# SimpleSeqArd_a10_added_missing_resistors.net
KiCad netlist of a schematic drawn in EAGLE
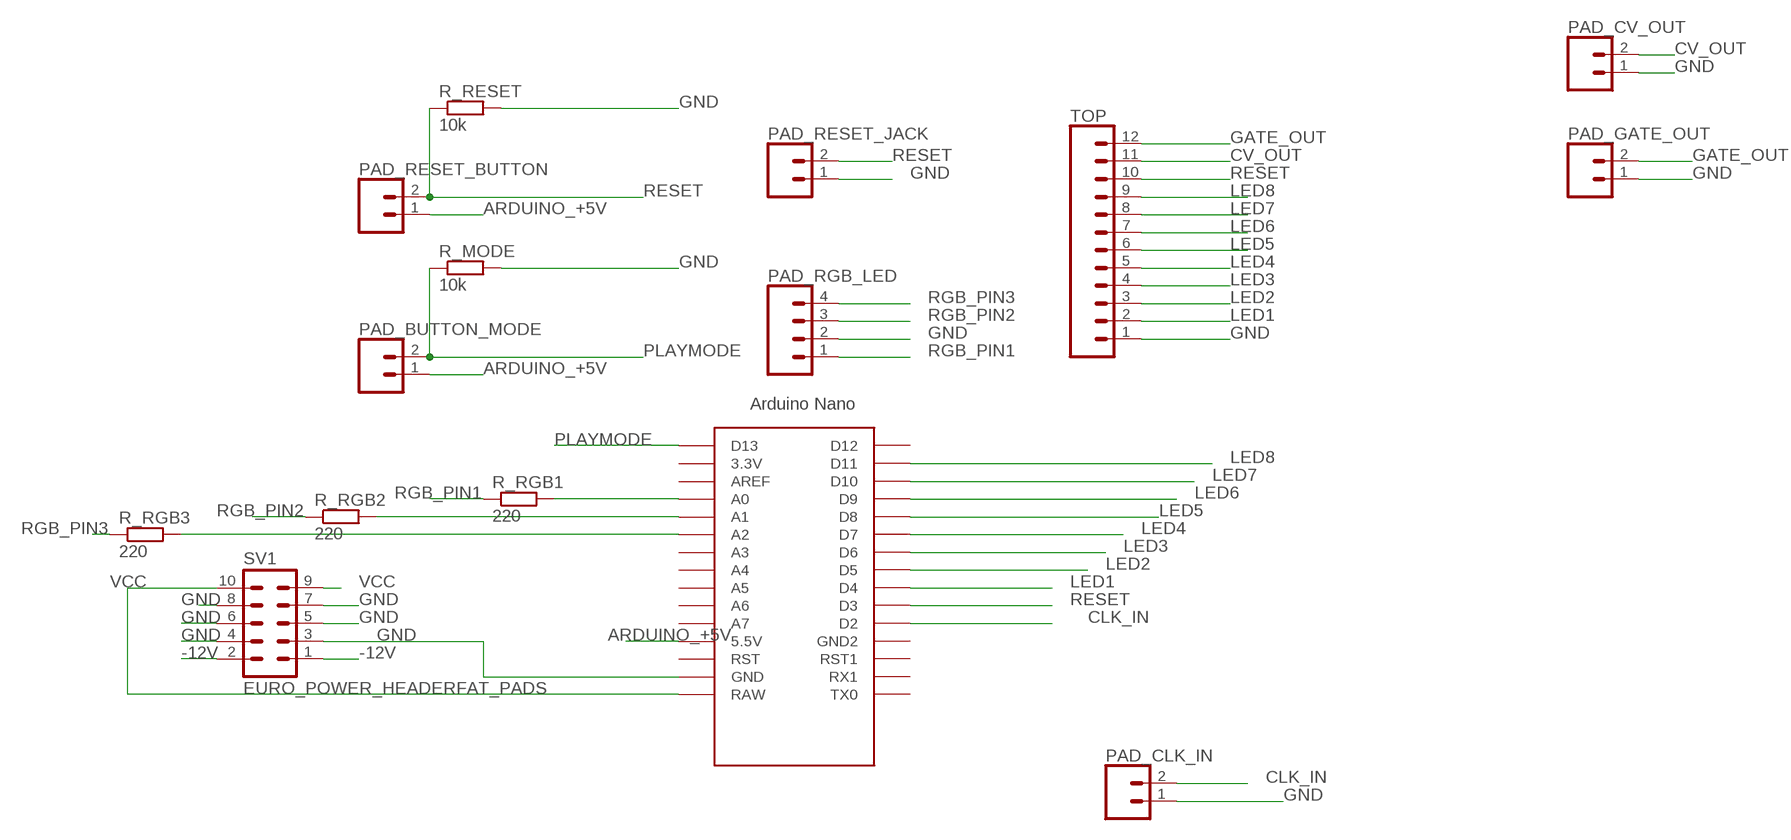
[diagram p0: schematic, sheet 1]

(export (version "E")
  (design (tool "Eeschema 10.0.6"))
  (components
    (comp (ref "PAD_BUTTON_MODE")
      (value "CONN_02PTH3")
      (footprint "eagle-import:1X02_LONGPADS")
      (libsource (lib "eagle-import") (part "CONN_02PTH3"))
    )
    (comp (ref "PAD_CLK_IN")
      (value "CONN_02PTH3")
      (footprint "eagle-import:1X02_LONGPADS")
      (libsource (lib "eagle-import") (part "CONN_02PTH3"))
    )
    (comp (ref "PAD_CV_OUT")
      (value "CONN_02PTH3")
      (footprint "eagle-import:1X02_LONGPADS")
      (libsource (lib "eagle-import") (part "CONN_02PTH3"))
    )
    (comp (ref "PAD_GATE_OUT")
      (value "CONN_02PTH3")
      (footprint "eagle-import:1X02_LONGPADS")
      (libsource (lib "eagle-import") (part "CONN_02PTH3"))
    )
    (comp (ref "PAD_RESET_BUTTON")
      (value "CONN_02PTH3")
      (footprint "eagle-import:1X02_LONGPADS")
      (libsource (lib "eagle-import") (part "CONN_02PTH3"))
    )
    (comp (ref "PAD_RESET_JACK")
      (value "CONN_02PTH3")
      (footprint "eagle-import:1X02_LONGPADS")
      (libsource (lib "eagle-import") (part "CONN_02PTH3"))
    )
    (comp (ref "PAD_RGB_LED")
      (value "CONN_04LONGPADS")
      (footprint "eagle-import:1X04_LONGPADS")
      (libsource (lib "eagle-import") (part "CONN_04LONGPADS"))
    )
    (comp (ref "R_MODE")
      (value "10k")
      (footprint "eagle-import:VERTICAL_RESISTOR")
      (libsource (lib "eagle-import") (part "RESISTORVERTICAL"))
    )
    (comp (ref "R_RESET")
      (value "10k")
      (footprint "eagle-import:VERTICAL_RESISTOR")
      (libsource (lib "eagle-import") (part "RESISTORVERTICAL"))
    )
    (comp (ref "R_RGB1")
      (value "220")
      (footprint "eagle-import:VERTICAL_RESISTOR")
      (libsource (lib "eagle-import") (part "RESISTORVERTICAL"))
    )
    (comp (ref "R_RGB2")
      (value "220")
      (footprint "eagle-import:VERTICAL_RESISTOR")
      (libsource (lib "eagle-import") (part "RESISTORVERTICAL"))
    )
    (comp (ref "R_RGB3")
      (value "220")
      (footprint "eagle-import:VERTICAL_RESISTOR")
      (libsource (lib "eagle-import") (part "RESISTORVERTICAL"))
    )
    (comp (ref "SV1")
      (value "EURO_POWER_HEADERFAT_PADS")
      (footprint "eagle-import:EURO_PWR_HEADER_FAT")
      (libsource (lib "eagle-import") (part "EURO_POWER_HEADERFAT_PADS"))
    )
    (comp (ref "TOP")
      (value "CONN_12LONGPADS")
      (footprint "eagle-import:1X12_LONGPADS")
      (libsource (lib "eagle-import") (part "CONN_12LONGPADS"))
    )
    (comp (ref "U$1")
      (value "NANO")
      (footprint "eagle-import:NANO")
      (libsource (lib "eagle-import") (part "NANO"))
    )
  )
  (nets
    (net (code "1") (name "/-12V") (class "Default")
      (node (ref "SV1") (pin "1") (pinfunction "1_1") (pintype "passive"))
      (node (ref "SV1") (pin "2") (pinfunction "2_2") (pintype "passive"))
    )
    (net (code "2") (name "/ARDUINO_+5V") (class "Default")
      (node (ref "PAD_BUTTON_MODE") (pin "1") (pinfunction "1_1") (pintype "passive"))
      (node (ref "PAD_RESET_BUTTON") (pin "1") (pinfunction "1_1") (pintype "passive"))
      (node (ref "U$1") (pin "5V") (pinfunction "5.5V_5V") (pintype "bidirectional"))
    )
    (net (code "3") (name "/CLK_IN") (class "Default")
      (node (ref "PAD_CLK_IN") (pin "2") (pinfunction "2_2") (pintype "passive"))
      (node (ref "U$1") (pin "D2") (pinfunction "D2_D2") (pintype "bidirectional"))
    )
    (net (code "4") (name "/CV_OUT") (class "Default")
      (node (ref "PAD_CV_OUT") (pin "2") (pinfunction "2_2") (pintype "passive"))
      (node (ref "TOP") (pin "11") (pinfunction "11_11") (pintype "passive"))
    )
    (net (code "5") (name "/GATE_OUT") (class "Default")
      (node (ref "PAD_GATE_OUT") (pin "2") (pinfunction "2_2") (pintype "passive"))
      (node (ref "TOP") (pin "12") (pinfunction "12_12") (pintype "passive"))
    )
    (net (code "6") (name "/GND") (class "Default")
      (node (ref "PAD_CLK_IN") (pin "1") (pinfunction "1_1") (pintype "passive"))
      (node (ref "PAD_CV_OUT") (pin "1") (pinfunction "1_1") (pintype "passive"))
      (node (ref "PAD_GATE_OUT") (pin "1") (pinfunction "1_1") (pintype "passive"))
      (node (ref "PAD_RESET_JACK") (pin "1") (pinfunction "1_1") (pintype "passive"))
      (node (ref "PAD_RGB_LED") (pin "2") (pinfunction "2_2") (pintype "passive"))
      (node (ref "R_MODE") (pin "2") (pinfunction "2_2") (pintype "passive"))
      (node (ref "R_RESET") (pin "2") (pinfunction "2_2") (pintype "passive"))
      (node (ref "SV1") (pin "3") (pinfunction "3_3") (pintype "passive"))
      (node (ref "SV1") (pin "4") (pinfunction "4_4") (pintype "passive"))
      (node (ref "SV1") (pin "5") (pinfunction "5_5") (pintype "passive"))
      (node (ref "SV1") (pin "6") (pinfunction "6_6") (pintype "passive"))
      (node (ref "SV1") (pin "7") (pinfunction "7_7") (pintype "passive"))
      (node (ref "SV1") (pin "8") (pinfunction "8_8") (pintype "passive"))
      (node (ref "TOP") (pin "1") (pinfunction "1_1") (pintype "passive"))
      (node (ref "U$1") (pin "GND") (pinfunction "GND_GND") (pintype "bidirectional"))
    )
    (net (code "7") (name "/LED1") (class "Default")
      (node (ref "TOP") (pin "2") (pinfunction "2_2") (pintype "passive"))
      (node (ref "U$1") (pin "D4") (pinfunction "D4_D4") (pintype "bidirectional"))
    )
    (net (code "8") (name "/LED2") (class "Default")
      (node (ref "TOP") (pin "3") (pinfunction "3_3") (pintype "passive"))
      (node (ref "U$1") (pin "D5") (pinfunction "D5_D5") (pintype "bidirectional"))
    )
    (net (code "9") (name "/LED3") (class "Default")
      (node (ref "TOP") (pin "4") (pinfunction "4_4") (pintype "passive"))
      (node (ref "U$1") (pin "D6") (pinfunction "D6_D6") (pintype "bidirectional"))
    )
    (net (code "10") (name "/LED4") (class "Default")
      (node (ref "TOP") (pin "5") (pinfunction "5_5") (pintype "passive"))
      (node (ref "U$1") (pin "D7") (pinfunction "D7_D7") (pintype "bidirectional"))
    )
    (net (code "11") (name "/LED5") (class "Default")
      (node (ref "TOP") (pin "6") (pinfunction "6_6") (pintype "passive"))
      (node (ref "U$1") (pin "D8") (pinfunction "D8_D8") (pintype "bidirectional"))
    )
    (net (code "12") (name "/LED6") (class "Default")
      (node (ref "TOP") (pin "7") (pinfunction "7_7") (pintype "passive"))
      (node (ref "U$1") (pin "D9") (pinfunction "D9_D9") (pintype "bidirectional"))
    )
    (net (code "13") (name "/LED7") (class "Default")
      (node (ref "TOP") (pin "8") (pinfunction "8_8") (pintype "passive"))
      (node (ref "U$1") (pin "D10") (pinfunction "D10_D10") (pintype "bidirectional"))
    )
    (net (code "14") (name "/LED8") (class "Default")
      (node (ref "TOP") (pin "9") (pinfunction "9_9") (pintype "passive"))
      (node (ref "U$1") (pin "D11") (pinfunction "D11_D11") (pintype "bidirectional"))
    )
    (net (code "15") (name "/PLAYMODE") (class "Default")
      (node (ref "PAD_BUTTON_MODE") (pin "2") (pinfunction "2_2") (pintype "passive"))
      (node (ref "R_MODE") (pin "1") (pinfunction "1_1") (pintype "passive"))
      (node (ref "U$1") (pin "D13") (pinfunction "D13_D13") (pintype "bidirectional"))
    )
    (net (code "16") (name "/RESET") (class "Default")
      (node (ref "PAD_RESET_BUTTON") (pin "2") (pinfunction "2_2") (pintype "passive"))
      (node (ref "PAD_RESET_JACK") (pin "2") (pinfunction "2_2") (pintype "passive"))
      (node (ref "R_RESET") (pin "1") (pinfunction "1_1") (pintype "passive"))
      (node (ref "TOP") (pin "10") (pinfunction "10_10") (pintype "passive"))
      (node (ref "U$1") (pin "D3") (pinfunction "D3_D3") (pintype "bidirectional"))
    )
    (net (code "17") (name "/RGB_PIN1") (class "Default")
      (node (ref "PAD_RGB_LED") (pin "1") (pinfunction "1_1") (pintype "passive"))
      (node (ref "R_RGB1") (pin "1") (pinfunction "1_1") (pintype "passive"))
    )
    (net (code "18") (name "/RGB_PIN2") (class "Default")
      (node (ref "PAD_RGB_LED") (pin "3") (pinfunction "3_3") (pintype "passive"))
      (node (ref "R_RGB2") (pin "1") (pinfunction "1_1") (pintype "passive"))
    )
    (net (code "19") (name "/RGB_PIN3") (class "Default")
      (node (ref "PAD_RGB_LED") (pin "4") (pinfunction "4_4") (pintype "passive"))
      (node (ref "R_RGB3") (pin "1") (pinfunction "1_1") (pintype "passive"))
    )
    (net (code "20") (name "/VCC") (class "Default")
      (node (ref "SV1") (pin "10") (pinfunction "10_10") (pintype "passive"))
      (node (ref "SV1") (pin "9") (pinfunction "9_9") (pintype "passive"))
      (node (ref "U$1") (pin "RAW") (pinfunction "RAW_RAW") (pintype "bidirectional"))
    )
    (net (code "21") (name "Net-(R_RGB1-Pad2)") (class "Default")
      (node (ref "R_RGB1") (pin "2") (pinfunction "2_2") (pintype "passive"))
      (node (ref "U$1") (pin "A0") (pinfunction "A0_A0") (pintype "bidirectional"))
    )
    (net (code "22") (name "Net-(R_RGB2-Pad2)") (class "Default")
      (node (ref "R_RGB2") (pin "2") (pinfunction "2_2") (pintype "passive"))
      (node (ref "U$1") (pin "A1") (pinfunction "A1_A1") (pintype "bidirectional"))
    )
    (net (code "23") (name "Net-(R_RGB3-Pad2)") (class "Default")
      (node (ref "R_RGB3") (pin "2") (pinfunction "2_2") (pintype "passive"))
      (node (ref "U$1") (pin "A2") (pinfunction "A2_A2") (pintype "bidirectional"))
    )
    (net (code "24") (name "unconnected-(U$1-GND2-PadGND1)") (class "Default")
      (node (ref "U$1") (pin "GND1") (pinfunction "GND2_GND1") (pintype "bidirectional"))
    )
    (net (code "25") (name "unconnected-(U$1-Pad3.3V)") (class "Default")
      (node (ref "U$1") (pin "3.3V") (pinfunction "3.3V_3.3V") (pintype "bidirectional"))
    )
    (net (code "26") (name "unconnected-(U$1-PadA3)") (class "Default")
      (node (ref "U$1") (pin "A3") (pinfunction "A3_A3") (pintype "bidirectional"))
    )
    (net (code "27") (name "unconnected-(U$1-PadA4)") (class "Default")
      (node (ref "U$1") (pin "A4") (pinfunction "A4_A4") (pintype "bidirectional"))
    )
    (net (code "28") (name "unconnected-(U$1-PadA5)") (class "Default")
      (node (ref "U$1") (pin "A5") (pinfunction "A5_A5") (pintype "bidirectional"))
    )
    (net (code "29") (name "unconnected-(U$1-PadA6)") (class "Default")
      (node (ref "U$1") (pin "A6") (pinfunction "A6_A6") (pintype "bidirectional"))
    )
    (net (code "30") (name "unconnected-(U$1-PadA7)") (class "Default")
      (node (ref "U$1") (pin "A7") (pinfunction "A7_A7") (pintype "bidirectional"))
    )
    (net (code "31") (name "unconnected-(U$1-PadAREF)") (class "Default")
      (node (ref "U$1") (pin "AREF") (pinfunction "AREF_AREF") (pintype "bidirectional"))
    )
    (net (code "32") (name "unconnected-(U$1-PadD12)") (class "Default")
      (node (ref "U$1") (pin "D12") (pinfunction "D12_D12") (pintype "bidirectional"))
    )
    (net (code "33") (name "unconnected-(U$1-PadRST)") (class "Default")
      (node (ref "U$1") (pin "RST") (pinfunction "RST_RST") (pintype "bidirectional"))
    )
    (net (code "34") (name "unconnected-(U$1-PadRST1)") (class "Default")
      (node (ref "U$1") (pin "RST1") (pinfunction "RST1_RST1") (pintype "bidirectional"))
    )
    (net (code "35") (name "unconnected-(U$1-PadRX1)") (class "Default")
      (node (ref "U$1") (pin "RX1") (pinfunction "RX1_RX1") (pintype "bidirectional"))
    )
    (net (code "36") (name "unconnected-(U$1-PadTX0)") (class "Default")
      (node (ref "U$1") (pin "TX0") (pinfunction "TX0_TX0") (pintype "bidirectional"))
    )
  )
)
